# board2side_small_nopwrcble.net
KiCad netlist of a schematic drawn in EAGLE
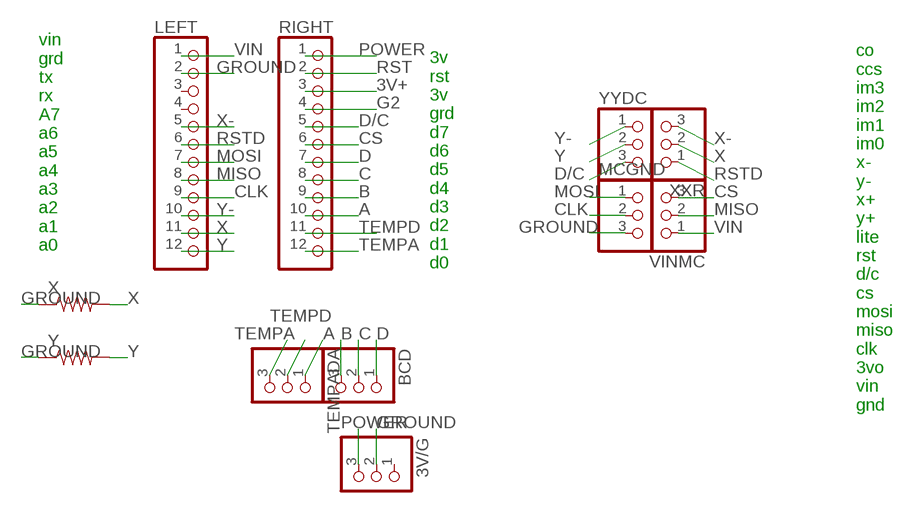
[diagram p0: schematic, sheet 1]

(export (version "E")
  (design (tool "Eeschema 10.0.6"))
  (components
    (comp (ref "3V/G")
      (value "PINHD-1X3CB")
      (footprint "eagle-import:1X03-CLEANBIG")
      (libsource (lib "eagle-import") (part "PINHD-1X3CB"))
    )
    (comp (ref "BCD")
      (value "PINHD-1X3CB")
      (footprint "eagle-import:1X03-CLEANBIG")
      (libsource (lib "eagle-import") (part "PINHD-1X3CB"))
    )
    (comp (ref "LEFT")
      (value "PINHD-1X12-CB")
      (footprint "eagle-import:1X12-CB")
      (libsource (lib "eagle-import") (part "PINHD-1X12-CB"))
    )
    (comp (ref "MCGND")
      (value "PINHD-1X3CB")
      (footprint "eagle-import:1X03-CLEANBIG")
      (libsource (lib "eagle-import") (part "PINHD-1X3CB"))
    )
    (comp (ref "RIGHT")
      (value "PINHD-1X12-CB")
      (footprint "eagle-import:1X12-CB")
      (libsource (lib "eagle-import") (part "PINHD-1X12-CB"))
    )
    (comp (ref "TEMPADA")
      (value "PINHD-1X3CB")
      (footprint "eagle-import:1X03-CLEANBIG")
      (libsource (lib "eagle-import") (part "PINHD-1X3CB"))
    )
    (comp (ref "VINMC")
      (value "PINHD-1X3CB")
      (footprint "eagle-import:1X03-CLEANBIG")
      (libsource (lib "eagle-import") (part "PINHD-1X3CB"))
    )
    (comp (ref "X")
      (value "10KOHM-1/6W-5%(PTH)KIT")
      (footprint "eagle-import:AXIAL-0.3-KIT")
      (libsource (lib "eagle-import") (part "10KOHM-1/6W-5%(PTH)KIT"))
    )
    (comp (ref "XXR")
      (value "PINHD-1X3CB")
      (footprint "eagle-import:1X03-CLEANBIG")
      (libsource (lib "eagle-import") (part "PINHD-1X3CB"))
    )
    (comp (ref "Y")
      (value "10KOHM-1/6W-5%(PTH)KIT")
      (footprint "eagle-import:AXIAL-0.3-KIT")
      (libsource (lib "eagle-import") (part "10KOHM-1/6W-5%(PTH)KIT"))
    )
    (comp (ref "YYDC")
      (value "PINHD-1X3CB")
      (footprint "eagle-import:1X03-CLEANBIG")
      (libsource (lib "eagle-import") (part "PINHD-1X3CB"))
    )
  )
  (nets
    (net (code "1") (name "/3V+") (class "Default")
      (node (ref "RIGHT") (pin "3") (pinfunction "3_3") (pintype "passive"))
    )
    (net (code "2") (name "/A") (class "Default")
      (node (ref "RIGHT") (pin "10") (pinfunction "10_10") (pintype "passive"))
      (node (ref "TEMPADA") (pin "1") (pinfunction "1_1") (pintype "passive"))
    )
    (net (code "3") (name "/B") (class "Default")
      (node (ref "BCD") (pin "3") (pinfunction "3_3") (pintype "passive"))
      (node (ref "RIGHT") (pin "9") (pinfunction "9_9") (pintype "passive"))
    )
    (net (code "4") (name "/C") (class "Default")
      (node (ref "BCD") (pin "2") (pinfunction "2_2") (pintype "passive"))
      (node (ref "RIGHT") (pin "8") (pinfunction "8_8") (pintype "passive"))
    )
    (net (code "5") (name "/CLK") (class "Default")
      (node (ref "LEFT") (pin "9") (pinfunction "9_9") (pintype "passive"))
      (node (ref "MCGND") (pin "2") (pinfunction "2_2") (pintype "passive"))
    )
    (net (code "6") (name "/CS") (class "Default")
      (node (ref "RIGHT") (pin "6") (pinfunction "6_6") (pintype "passive"))
      (node (ref "VINMC") (pin "3") (pinfunction "3_3") (pintype "passive"))
    )
    (net (code "7") (name "/D") (class "Default")
      (node (ref "BCD") (pin "1") (pinfunction "1_1") (pintype "passive"))
      (node (ref "RIGHT") (pin "7") (pinfunction "7_7") (pintype "passive"))
    )
    (net (code "8") (name "/D{slash}C") (class "Default")
      (node (ref "RIGHT") (pin "5") (pinfunction "5_5") (pintype "passive"))
      (node (ref "YYDC") (pin "3") (pinfunction "3_3") (pintype "passive"))
    )
    (net (code "9") (name "/G2") (class "Default")
      (node (ref "RIGHT") (pin "4") (pinfunction "4_4") (pintype "passive"))
    )
    (net (code "10") (name "/GROUND") (class "Default")
      (node (ref "3V/G") (pin "2") (pinfunction "2_2") (pintype "passive"))
      (node (ref "LEFT") (pin "2") (pinfunction "2_2") (pintype "passive"))
      (node (ref "MCGND") (pin "3") (pinfunction "3_3") (pintype "passive"))
      (node (ref "X") (pin "P$1") (pinfunction "1_P$1") (pintype "passive"))
      (node (ref "Y") (pin "P$1") (pinfunction "1_P$1") (pintype "passive"))
    )
    (net (code "11") (name "/MISO") (class "Default")
      (node (ref "LEFT") (pin "8") (pinfunction "8_8") (pintype "passive"))
      (node (ref "VINMC") (pin "2") (pinfunction "2_2") (pintype "passive"))
    )
    (net (code "12") (name "/MOSI") (class "Default")
      (node (ref "LEFT") (pin "7") (pinfunction "7_7") (pintype "passive"))
      (node (ref "MCGND") (pin "1") (pinfunction "1_1") (pintype "passive"))
    )
    (net (code "13") (name "/POWER") (class "Default")
      (node (ref "3V/G") (pin "3") (pinfunction "3_3") (pintype "passive"))
      (node (ref "RIGHT") (pin "1") (pinfunction "1_1") (pintype "passive"))
    )
    (net (code "14") (name "/RST") (class "Default")
      (node (ref "RIGHT") (pin "2") (pinfunction "2_2") (pintype "passive"))
    )
    (net (code "15") (name "/RSTD") (class "Default")
      (node (ref "LEFT") (pin "6") (pinfunction "6_6") (pintype "passive"))
      (node (ref "XXR") (pin "1") (pinfunction "1_1") (pintype "passive"))
    )
    (net (code "16") (name "/TEMPA") (class "Default")
      (node (ref "RIGHT") (pin "12") (pinfunction "12_12") (pintype "passive"))
      (node (ref "TEMPADA") (pin "3") (pinfunction "3_3") (pintype "passive"))
    )
    (net (code "17") (name "/TEMPD") (class "Default")
      (node (ref "RIGHT") (pin "11") (pinfunction "11_11") (pintype "passive"))
      (node (ref "TEMPADA") (pin "2") (pinfunction "2_2") (pintype "passive"))
    )
    (net (code "18") (name "/VIN") (class "Default")
      (node (ref "LEFT") (pin "1") (pinfunction "1_1") (pintype "passive"))
      (node (ref "VINMC") (pin "1") (pinfunction "1_1") (pintype "passive"))
    )
    (net (code "19") (name "/X") (class "Default")
      (node (ref "LEFT") (pin "11") (pinfunction "11_11") (pintype "passive"))
      (node (ref "X") (pin "P$2") (pinfunction "2_P$2") (pintype "passive"))
      (node (ref "XXR") (pin "2") (pinfunction "2_2") (pintype "passive"))
    )
    (net (code "20") (name "/X-") (class "Default")
      (node (ref "LEFT") (pin "5") (pinfunction "5_5") (pintype "passive"))
      (node (ref "XXR") (pin "3") (pinfunction "3_3") (pintype "passive"))
    )
    (net (code "21") (name "/Y") (class "Default")
      (node (ref "LEFT") (pin "12") (pinfunction "12_12") (pintype "passive"))
      (node (ref "Y") (pin "P$2") (pinfunction "2_P$2") (pintype "passive"))
      (node (ref "YYDC") (pin "2") (pinfunction "2_2") (pintype "passive"))
    )
    (net (code "22") (name "/Y-") (class "Default")
      (node (ref "LEFT") (pin "10") (pinfunction "10_10") (pintype "passive"))
      (node (ref "YYDC") (pin "1") (pinfunction "1_1") (pintype "passive"))
    )
    (net (code "23") (name "unconnected-(3V/G-Pad1)") (class "Default")
      (node (ref "3V/G") (pin "1") (pinfunction "1_1") (pintype "passive"))
    )
    (net (code "24") (name "unconnected-(LEFT-Pad3)") (class "Default")
      (node (ref "LEFT") (pin "3") (pinfunction "3_3") (pintype "passive"))
    )
    (net (code "25") (name "unconnected-(LEFT-Pad4)") (class "Default")
      (node (ref "LEFT") (pin "4") (pinfunction "4_4") (pintype "passive"))
    )
  )
)
